# Digital_Sensors.net
KiCad netlist of a schematic drawn in Altium Designer
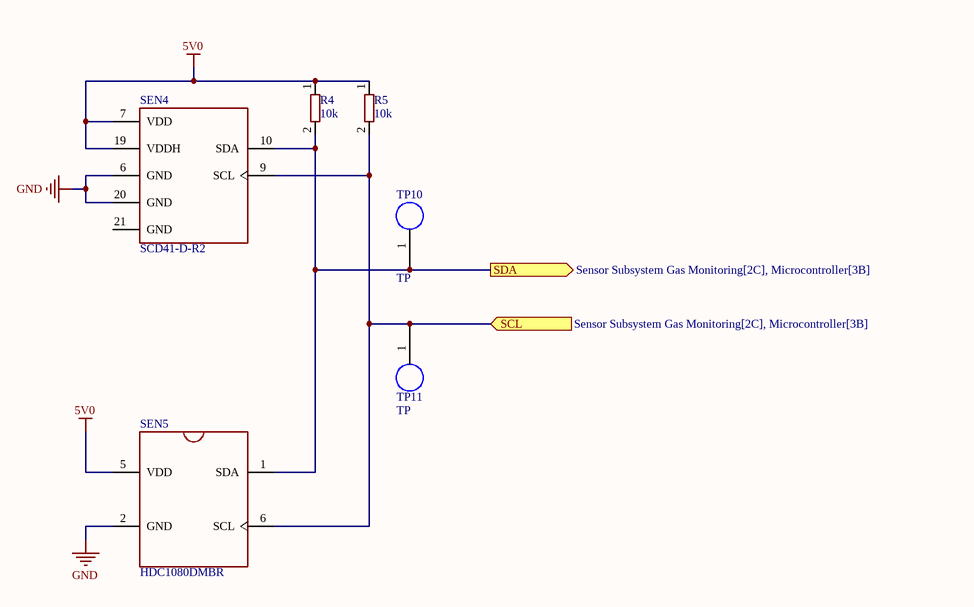
[diagram p0: Digital Sensors.SchDoc]

(export (version "E")
  (design (tool "Eeschema 10.0.6"))
  (components
    (comp (ref "R4")
      (value "10k")
      (footprint "10K Resistor:0603")
      (description "http://octopart.com/rc0603fr-1310kl-yageo+%2F+phycomp-25905087")
      (fields (field (name "MP") "RC0603FR-1310KL"))
      (libsource (lib "10K Resistor") (part "RC0603FR-1310KL"))
    )
    (comp (ref "R5")
      (value "10k")
      (footprint "10K Resistor:0603")
      (description "http://octopart.com/rc0603fr-1310kl-yageo+%2F+phycomp-25905087")
      (fields (field (name "MP") "RC0603FR-1310KL"))
      (libsource (lib "10K Resistor") (part "RC0603FR-1310KL"))
    )
    (comp (ref "SEN4")
      (value "SCD41-D-R2")
      (footprint "XDCR_SCD41-D-R2")
      (description "Air Quality Sensor CO2 Sensor 2.5V/3.3V/5V 20-Pin SMD EP")
      (fields (field (name "MF") "Sensirion AG"))
      (libsource (lib "CO2 Sensor") (part "SCD41-D-R2"))
    )
    (comp (ref "SEN5")
      (value "HDC1080DMBR")
      (footprint "Temp Sensor:SON100P300X300X80-7N")
      (description "Temperature and Humidity Sensor")
      (fields (field (name "MF") "Texas Instruments"))
      (libsource (lib "Temp Sensor") (part "HDC1080DMBR"))
    )
    (comp (ref "TP10")
      (value "TP")
      (footprint "TestPoint")
      (description "Test point for voltage, current, ect.")
      (libsource (lib "TestPoint") (part "TestPoint"))
    )
    (comp (ref "TP11")
      (value "TP")
      (footprint "TestPoint")
      (description "Test point for voltage, current, ect.")
      (libsource (lib "") (part "TestPoint_1"))
    )
  )
  (nets
    (net (code "1") (name "/SCL") (class "Default")
      (node (ref "R5") (pin "2") (pintype "passive"))
      (node (ref "SEN4") (pin "9") (pinfunction "SCL_9") (pintype "passive"))
      (node (ref "SEN5") (pin "6") (pinfunction "SCL_6") (pintype "passive"))
      (node (ref "TP11") (pin "1") (pintype "passive"))
    )
    (net (code "2") (name "/SDA") (class "Default")
      (node (ref "R4") (pin "2") (pintype "passive"))
      (node (ref "SEN4") (pin "10") (pinfunction "SDA_10") (pintype "passive"))
      (node (ref "SEN5") (pin "1") (pinfunction "SDA_1") (pintype "passive"))
      (node (ref "TP10") (pin "1") (pintype "passive"))
    )
    (net (code "3") (name "5V0") (class "Default")
      (node (ref "R4") (pin "1") (pintype "passive"))
      (node (ref "R5") (pin "1") (pintype "passive"))
      (node (ref "SEN4") (pin "19") (pinfunction "VDDH_19") (pintype "power_in"))
      (node (ref "SEN4") (pin "7") (pinfunction "VDD_7") (pintype "power_in"))
      (node (ref "SEN5") (pin "5") (pinfunction "VDD_5") (pintype "power_in"))
    )
    (net (code "4") (name "GND") (class "Default")
      (node (ref "SEN4") (pin "20") (pinfunction "GND_20") (pintype "power_in"))
      (node (ref "SEN4") (pin "6") (pinfunction "GND_6") (pintype "power_in"))
      (node (ref "SEN5") (pin "2") (pinfunction "GND_2") (pintype "power_in"))
    )
    (net (code "5") (name "unconnected-(SEN4-GND-Pad21)") (class "Default")
      (node (ref "SEN4") (pin "21") (pinfunction "GND_21") (pintype "power_in"))
    )
  )
)
